# RADG-USB-S03-V00.net
KiCad netlist of a schematic drawn in Altium Designer
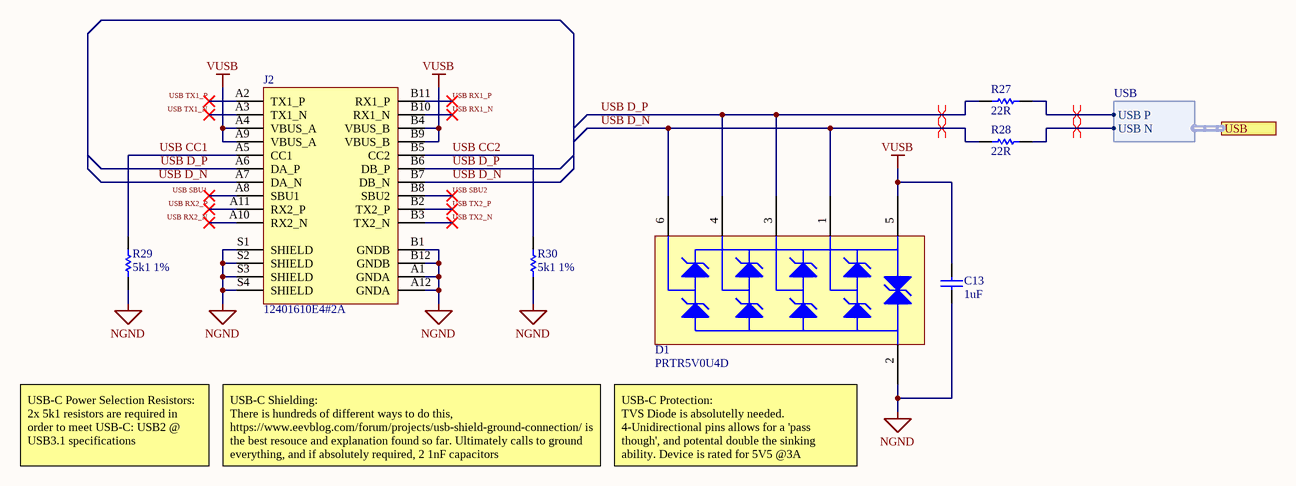
[diagram p0: RADG-USB-S03-V00.SchDoc]

(export (version "E")
  (design (tool "Eeschema 10.0.6"))
  (components
    (comp (ref "C13")
      (value "1uF")
      (footprint "Cap_Ceramic_0603")
      (description "Capacitor, Ceramic, SMD, 1uF, 25V, 5%, X7R, 0603")
      (libsource (lib "StandardCapacitors") (part "1uF 25V 5% X7R 0603"))
    )
    (comp (ref "D1")
      (value "PRTR5V0U4D")
      (footprint "SC-47")
      (description "Clamp Ipp Tvs Diode Surface Mount 6-TSOP")
      (libsource (lib "QUTMS_DiodeLibrary") (part "PRTR5V0U4D"))
    )
    (comp (ref "J2")
      (value "12401610E4#2A")
      (footprint "12401610E4#2A")
      (libsource (lib "QUTMS_USBLibrary") (part "12401610E4#2A"))
    )
    (comp (ref "R27")
      (value "22R")
      (footprint "Res_ThinFilm_0603")
      (description "Resistor, SMD, 22R, 0.1W, 5%, 0603")
      (libsource (lib "StandardResistors") (part "22R 5% 0603"))
    )
    (comp (ref "R28")
      (value "22R")
      (footprint "Res_ThinFilm_0603")
      (description "Resistor, SMD, 22R, 0.1W, 5%, 0603")
      (libsource (lib "StandardResistors") (part "22R 5% 0603"))
    )
    (comp (ref "R29")
      (value "5k1 1%")
      (footprint "Res_ThinFilm_0603")
      (description "Resistor, SMD, 5k1, 0.1W, 1%, 0603")
      (libsource (lib "StandardResistors") (part "5k1 1% 0603"))
    )
    (comp (ref "R30")
      (value "5k1 1%")
      (footprint "Res_ThinFilm_0603")
      (description "Resistor, SMD, 5k1, 0.1W, 1%, 0603")
      (libsource (lib "StandardResistors") (part "5k1 1% 0603"))
    )
  )
  (nets
    (net (code "2") (name "/USB CC1") (class "Default")
      (node (ref "J2") (pin "A5") (pinfunction "CC1_A5") (pintype "passive"))
      (node (ref "R29") (pin "2") (pinfunction "2_2") (pintype "passive"))
    )
    (net (code "3") (name "/USB CC2") (class "Default")
      (node (ref "J2") (pin "B5") (pinfunction "CC2_B5") (pintype "passive"))
      (node (ref "R30") (pin "2") (pinfunction "2_2") (pintype "passive"))
    )
    (net (code "4") (name "/USB D_N") (class "Default")
      (node (ref "D1") (pin "1") (pinfunction "P1_1") (pintype "passive"))
      (node (ref "D1") (pin "6") (pinfunction "P4_6") (pintype "passive"))
      (node (ref "J2") (pin "A7") (pinfunction "DA_N_A7") (pintype "passive"))
      (node (ref "J2") (pin "B7") (pinfunction "DB_N_B7") (pintype "passive"))
      (node (ref "R28") (pin "1") (pinfunction "1_1") (pintype "passive"))
    )
    (net (code "5") (name "/USB D_P") (class "Default")
      (node (ref "D1") (pin "3") (pinfunction "P2_3") (pintype "passive"))
      (node (ref "D1") (pin "4") (pinfunction "P3_4") (pintype "passive"))
      (node (ref "J2") (pin "A6") (pinfunction "DA_P_A6") (pintype "passive"))
      (node (ref "J2") (pin "B6") (pinfunction "DB_P_B6") (pintype "passive"))
      (node (ref "R27") (pin "1") (pinfunction "1_1") (pintype "passive"))
    )
    (net (code "6") (name "/USB N") (class "Default")
      (node (ref "R28") (pin "2") (pinfunction "2_2") (pintype "passive"))
    )
    (net (code "7") (name "/USB P") (class "Default")
      (node (ref "R27") (pin "2") (pinfunction "2_2") (pintype "passive"))
    )
    (net (code "8") (name "/USB RX1_N") (class "Default")
      (node (ref "J2") (pin "B10") (pinfunction "RX1_N_B10") (pintype "passive+no_connect"))
    )
    (net (code "9") (name "/USB RX1_P") (class "Default")
      (node (ref "J2") (pin "B11") (pinfunction "RX1_P_B11") (pintype "passive+no_connect"))
    )
    (net (code "10") (name "/USB RX2_N") (class "Default")
      (node (ref "J2") (pin "A10") (pinfunction "RX2_N_A10") (pintype "passive+no_connect"))
    )
    (net (code "11") (name "/USB RX2_P") (class "Default")
      (node (ref "J2") (pin "A11") (pinfunction "RX2_P_A11") (pintype "passive+no_connect"))
    )
    (net (code "12") (name "/USB SBU1") (class "Default")
      (node (ref "J2") (pin "A8") (pinfunction "SBU1_A8") (pintype "passive+no_connect"))
    )
    (net (code "13") (name "/USB SBU2") (class "Default")
      (node (ref "J2") (pin "B8") (pinfunction "SBU2_B8") (pintype "passive+no_connect"))
    )
    (net (code "14") (name "/USB TX1_N") (class "Default")
      (node (ref "J2") (pin "A3") (pinfunction "TX1_N_A3") (pintype "passive+no_connect"))
    )
    (net (code "15") (name "/USB TX1_P") (class "Default")
      (node (ref "J2") (pin "A2") (pinfunction "TX1_P_A2") (pintype "passive+no_connect"))
    )
    (net (code "16") (name "/USB TX2_N") (class "Default")
      (node (ref "J2") (pin "B3") (pinfunction "TX2_N_B3") (pintype "passive+no_connect"))
    )
    (net (code "17") (name "/USB TX2_P") (class "Default")
      (node (ref "J2") (pin "B2") (pinfunction "TX2_P_B2") (pintype "passive+no_connect"))
    )
    (net (code "19") (name "NGND") (class "Default")
      (node (ref "C13") (pin "1") (pinfunction "1_1") (pintype "passive"))
      (node (ref "D1") (pin "2") (pinfunction "GND_2") (pintype "passive"))
      (node (ref "J2") (pin "A1") (pinfunction "GNDA_A1") (pintype "passive"))
      (node (ref "J2") (pin "A12") (pinfunction "GNDA_A12") (pintype "passive"))
      (node (ref "J2") (pin "B1") (pinfunction "GNDB_B1") (pintype "passive"))
      (node (ref "J2") (pin "B12") (pinfunction "GNDB_B12") (pintype "passive"))
      (node (ref "J2") (pin "S1") (pinfunction "SHIELD_S1") (pintype "power_in"))
      (node (ref "J2") (pin "S2") (pinfunction "SHIELD_S2") (pintype "power_in"))
      (node (ref "J2") (pin "S3") (pinfunction "SHIELD_S3") (pintype "power_in"))
      (node (ref "J2") (pin "S4") (pinfunction "SHIELD_S4") (pintype "power_in"))
      (node (ref "R29") (pin "1") (pinfunction "1_1") (pintype "passive"))
      (node (ref "R30") (pin "1") (pinfunction "1_1") (pintype "passive"))
    )
    (net (code "20") (name "VUSB") (class "Default")
      (node (ref "C13") (pin "2") (pinfunction "2_2") (pintype "passive"))
      (node (ref "D1") (pin "5") (pinfunction "VCC_5") (pintype "passive"))
      (node (ref "J2") (pin "A4") (pinfunction "VBUS_A_A4") (pintype "passive"))
      (node (ref "J2") (pin "A9") (pinfunction "VBUS_A_A9") (pintype "passive"))
      (node (ref "J2") (pin "B4") (pinfunction "VBUS_B_B4") (pintype "passive"))
      (node (ref "J2") (pin "B9") (pinfunction "VBUS_B_B9") (pintype "passive"))
    )
  )
)
